# LatchDelay.net
KiCad netlist of a schematic drawn in Altium Designer
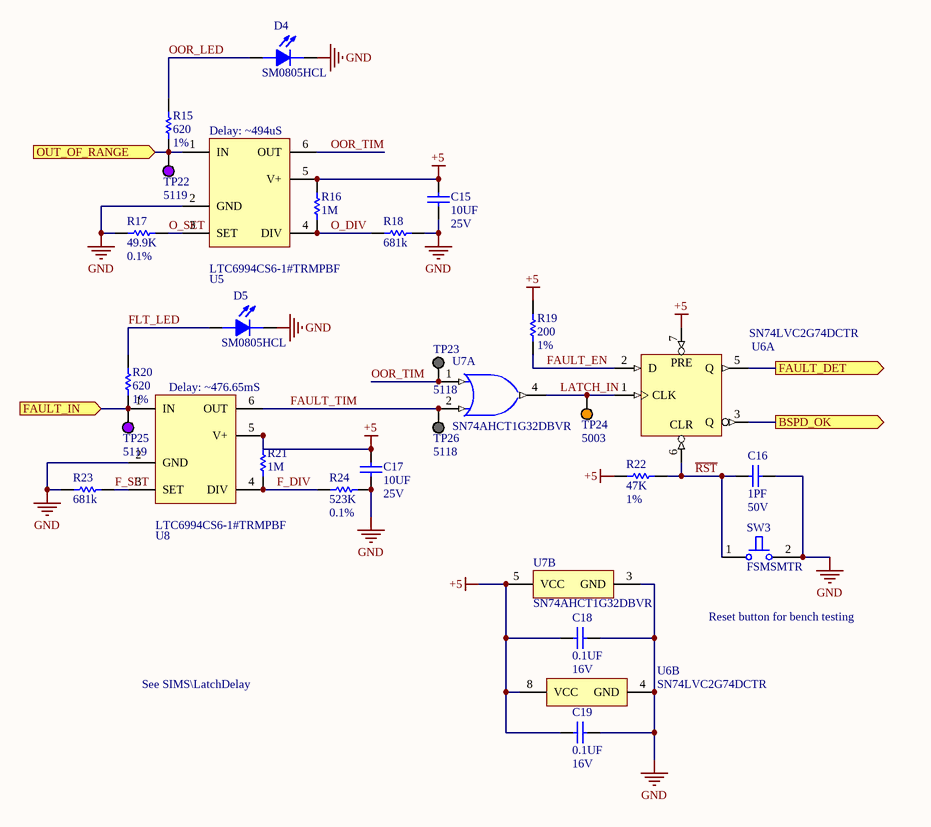
[diagram p0: LatchDelay.SchDoc]

(export (version "E")
  (design (tool "Eeschema 10.0.6"))
  (components
    (comp (ref "C15")
      (value "CAP 0603 10UF 25V 20% X5R")
      (footprint "0603_CAP")
      (description "Capacitor Surface Mount 0603 Footprint 10UF 25V 20% Tolerance Ceramic X5R")
      (fields
        (field (name "VAL") "10UF")
        (field (name "VOL") "25V")
        (field (name "MANUFACTURER") "Various")
        (field (name "VOLTAGE") "25V")
      )
      (libsource (lib "Passive Components") (part "cap"))
    )
    (comp (ref "C16")
      (value "CAP 0603 1PF 50V 0.05PF MLO")
      (footprint "0603_CAP")
      (description "Capacitor Surface Mount 0603 Footprint 1PF 50V 0.05PF Tolerance MLO")
      (fields
        (field (name "VAL") "1PF")
        (field (name "VOL") "50V")
        (field (name "MANUFACTURER") "Various")
        (field (name "VOLTAGE") "50V")
      )
      (libsource (lib "Passive Components") (part "cap"))
    )
    (comp (ref "C17")
      (value "CAP 0603 10UF 25V 20% X5R")
      (footprint "0603_CAP")
      (description "Capacitor Surface Mount 0603 Footprint 10UF 25V 20% Tolerance Ceramic X5R")
      (fields
        (field (name "VAL") "10UF")
        (field (name "VOL") "25V")
        (field (name "MANUFACTURER") "Various")
        (field (name "VOLTAGE") "25V")
      )
      (libsource (lib "Passive Components") (part "cap"))
    )
    (comp (ref "C18")
      (value "CAP 0603 0.1UF 16V 10% X7R")
      (footprint "0603_CAP")
      (description "Capacitor Surface Mount 0603 Footprint 0.1UF 16V 10% Tolerance Ceramic X7R")
      (fields
        (field (name "VAL") "0.1UF")
        (field (name "VOL") "16V")
        (field (name "MANUFACTURER") "Various")
        (field (name "VOLTAGE") "16V")
      )
      (libsource (lib "Passive Components") (part "cap"))
    )
    (comp (ref "C19")
      (value "CAP 0603 0.1UF 16V 10% X7R")
      (footprint "0603_CAP")
      (description "Capacitor Surface Mount 0603 Footprint 0.1UF 16V 10% Tolerance Ceramic X7R")
      (fields
        (field (name "VAL") "0.1UF")
        (field (name "VOL") "16V")
        (field (name "MANUFACTURER") "Various")
        (field (name "VOLTAGE") "16V")
      )
      (libsource (lib "Passive Components") (part "cap"))
    )
    (comp (ref "D4")
      (value "SM0805HCL")
      (footprint "LEDC2012X135N_SM0805HCL(Primary)")
      (description "Red 631nm LED Indication - Discrete 1.9V 0805 (2012 Metric)")
      (libsource (lib "bspd parts") (part "SM0805HCL"))
    )
    (comp (ref "D5")
      (value "SM0805HCL")
      (footprint "LEDC2012X135N_SM0805HCL(Primary)")
      (description "Red 631nm LED Indication - Discrete 1.9V 0805 (2012 Metric)")
      (libsource (lib "bspd parts") (part "SM0805HCL"))
    )
    (comp (ref "R15")
      (value "RES 0603 620 1%")
      (footprint "0603_RES")
      (description "Resistor Surface Mount, 620 Ohms, 0603 Footprint, 1% Tolerance 0.1W")
      (fields
        (field (name "VAL") "620")
        (field (name "TOL") "1%")
        (field (name "MANUFACTURER") "Various")
        (field (name "TOLERANCE") "1%")
      )
      (libsource (lib "Passive Components") (part "res"))
    )
    (comp (ref "R16")
      (value "1M")
      (footprint "RESC2013X60X35ML10T20")
      (fields (field (name "MANUFACTURER") "Yageo") (field (name "PART NUMBER") "RT0805BRE071ML"))
      (libsource (lib "Altium Content Vault") (part "RES"))
    )
    (comp (ref "R17")
      (value "RES 0603 49.9K 0.1%")
      (footprint "0603_RES")
      (description "Resistor Surface Mount, 49.9K Ohms, 0603 Footprint, 0.1% Tolerance 0.1W")
      (fields
        (field (name "VAL") "49.9K")
        (field (name "TOL") "0.1%")
        (field (name "MANUFACTURER") "Various")
        (field (name "TOLERANCE") "0.1%")
      )
      (libsource (lib "Passive Components") (part "res"))
    )
    (comp (ref "R18")
      (value "681k")
      (footprint "RESC2013X60X40NL20T25")
      (fields (field (name "MANUFACTURER") "Panasonic") (field (name "PART NUMBER") "ERA6AEB6813V"))
      (libsource (lib "Altium Content Vault") (part "RES"))
    )
    (comp (ref "R19")
      (value "RES 0603 200 1%")
      (footprint "0603_RES")
      (description "Resistor Surface Mount, 200 Ohms, 0603 Footprint, 1% Tolerance 0.1W")
      (fields
        (field (name "VAL") "200")
        (field (name "TOL") "1%")
        (field (name "MANUFACTURER") "Various")
        (field (name "TOLERANCE") "1%")
      )
      (libsource (lib "Passive Components") (part "res"))
    )
    (comp (ref "R20")
      (value "RES 0603 620 1%")
      (footprint "0603_RES")
      (description "Resistor Surface Mount, 620 Ohms, 0603 Footprint, 1% Tolerance 0.1W")
      (fields
        (field (name "VAL") "620")
        (field (name "TOL") "1%")
        (field (name "MANUFACTURER") "Various")
        (field (name "TOLERANCE") "1%")
      )
      (libsource (lib "Passive Components") (part "res"))
    )
    (comp (ref "R21")
      (value "1M")
      (footprint "RESC2013X60X35ML10T20")
      (fields (field (name "MANUFACTURER") "Yageo") (field (name "PART NUMBER") "RT0805BRE071ML"))
      (libsource (lib "Altium Content Vault") (part "RES"))
    )
    (comp (ref "R22")
      (value "RES 0603 47K 1%")
      (footprint "0603_RES")
      (description "Resistor Surface Mount, 47K Ohms, 0603 Footprint, 1% Tolerance 0.1W")
      (fields
        (field (name "VAL") "47K")
        (field (name "TOL") "1%")
        (field (name "MANUFACTURER") "Various")
        (field (name "TOLERANCE") "1%")
      )
      (libsource (lib "Passive Components") (part "res"))
    )
    (comp (ref "R23")
      (value "681k")
      (footprint "RESC2013X60X40NL20T25")
      (fields (field (name "MANUFACTURER") "Panasonic") (field (name "PART NUMBER") "ERA6AEB6813V"))
      (libsource (lib "Altium Content Vault") (part "RES"))
    )
    (comp (ref "R24")
      (value "RES 0805 523K 0.1%")
      (footprint "0805_RES")
      (description "Resistor Surface Mount, 523K Ohms, 0805 Footprint, 0.1% Tolerance 0.125W")
      (fields
        (field (name "VAL") "523K")
        (field (name "TOL") "0.1%")
        (field (name "MANUFACTURER") "Various")
        (field (name "TOLERANCE") "0.1%")
      )
      (libsource (lib "Passive Components") (part "res"))
    )
    (comp (ref "SW3")
      (value "FSMSMTR")
      (footprint "TECO-FSMSMTR_V")
      (description "FSMSM Push Button Switch, 50 mA, -35 to 85 degC, 2-Pin SMD, RoHS, Tape and Reel")
      (fields (field (name "MANUFACTURER") "TE Connectivity"))
      (libsource (lib "bspd parts") (part "FSMSMTR"))
    )
    (comp (ref "TP22")
      (value "5119")
      (footprint "KSTN-5119")
      (description "Test Point, Purple, 1-Pin THD, RoHS, Bulk")
      (fields (field (name "MANUFACTURER") "KeystoneElectronics"))
      (libsource (lib "bspd parts") (part "5119"))
    )
    (comp (ref "TP23")
      (value "5118")
      (footprint "KSTN-5118")
      (description "Test Point, Grey, 1-Pin THD, RoHS, Bulk")
      (fields (field (name "MANUFACTURER") "KeystoneElectronics"))
      (libsource (lib "bspd parts") (part "5118"))
    )
    (comp (ref "TP24")
      (value "5003")
      (footprint "KSTN-5003")
      (description "Test Point, Orange, 1-Pin THD, RoHS, Bulk")
      (fields (field (name "MANUFACTURER") "KeystoneElectronics"))
      (libsource (lib "bspd parts") (part "5003"))
    )
    (comp (ref "TP25")
      (value "5119")
      (footprint "KSTN-5119")
      (description "Test Point, Purple, 1-Pin THD, RoHS, Bulk")
      (fields (field (name "MANUFACTURER") "KeystoneElectronics"))
      (libsource (lib "bspd parts") (part "5119"))
    )
    (comp (ref "TP26")
      (value "5118")
      (footprint "KSTN-5118")
      (description "Test Point, Grey, 1-Pin THD, RoHS, Bulk")
      (fields (field (name "MANUFACTURER") "KeystoneElectronics"))
      (libsource (lib "bspd parts") (part "5118"))
    )
    (comp (ref "U5")
      (value "LTC6994CS6-1#TRMPBF")
      (footprint "Linear_Technologies_LTC6994CS6-1#TRMPBF_0")
      (description "IC DELAY LINE 8TAP PROG TSOT23-6")
      (fields
        (field (name "DIGIKEY PART NUMBER") "LTC6994CS6-1#TRMPBFCT-ND")
        (field (name "MANUFACTURER") "Linear Technologies")
      )
      (libsource (lib "bspd parts") (part "LTC6994CS6-1#TRMPBF"))
    )
    (comp (ref "U6")
      (value "SN74LVC2G74DCTR")
      (footprint "DCT0008A_M")
      (description "Single Positive-Edge-Triggered D-Type Flip-Flop with Clear and Preset, DCT0008A, LARGE T&R")
      (fields
        (field (name "GENERIC PART NUMBER") "SN74LVC2G74")
        (field (name "MANUFACTURER") "Texas Instruments")
      )
      (libsource (lib "Altium Content Vault") (part "TI-SN74XXX1G74_2G74-8"))
    )
    (comp (ref "U7")
      (value "SN74AHCT1G32DBVR")
      (footprint "DBV0005A_M")
      (description "Single 2-Input Positive-OR Gate, DBV0005A, LARGE T&R")
      (fields
        (field (name "GENERIC PART NUMBER") "SN74AHCT1G32")
        (field (name "MANUFACTURER") "Texas Instruments")
      )
      (libsource (lib "Altium Content Vault") (part "TI-SN74XXX1X32-5"))
    )
    (comp (ref "U8")
      (value "LTC6994CS6-1#TRMPBF")
      (footprint "Linear_Technologies_LTC6994CS6-1#TRMPBF_0")
      (description "IC DELAY LINE 8TAP PROG TSOT23-6")
      (fields
        (field (name "DIGIKEY PART NUMBER") "LTC6994CS6-1#TRMPBFCT-ND")
        (field (name "MANUFACTURER") "Linear Technologies")
      )
      (libsource (lib "bspd parts") (part "LTC6994CS6-1#TRMPBF"))
    )
  )
  (nets
    (net (code "1") (name "+5") (class "Default")
      (node (ref "C15") (pin "2") (pinfunction "2_2") (pintype "passive"))
      (node (ref "C17") (pin "2") (pinfunction "2_2") (pintype "passive"))
      (node (ref "C18") (pin "2") (pinfunction "2_2") (pintype "passive"))
      (node (ref "C19") (pin "2") (pinfunction "2_2") (pintype "passive"))
      (node (ref "R16") (pin "2") (pinfunction "2_2") (pintype "passive"))
      (node (ref "R19") (pin "2") (pinfunction "2_2") (pintype "passive"))
      (node (ref "R21") (pin "2") (pinfunction "2_2") (pintype "passive"))
      (node (ref "R22") (pin "1") (pinfunction "1_1") (pintype "passive"))
      (node (ref "U5") (pin "5") (pinfunction "V+_5") (pintype "passive"))
      (node (ref "U6") (pin "7") (pinfunction "~{PRE}_7") (pintype "input"))
      (node (ref "U6") (pin "8") (pinfunction "VCC_8") (pintype "power_in"))
      (node (ref "U7") (pin "5") (pinfunction "VCC_5") (pintype "power_in"))
      (node (ref "U8") (pin "5") (pinfunction "V+_5") (pintype "passive"))
    )
    (net (code "2") (name "/BSPD_OK") (class "Default")
      (node (ref "U6") (pin "3") (pinfunction "Q_3") (pintype "output"))
    )
    (net (code "3") (name "/FAULT_DET") (class "Default")
      (node (ref "U6") (pin "5") (pinfunction "Q_5") (pintype "output"))
    )
    (net (code "4") (name "/FAULT_EN") (class "Default")
      (node (ref "R19") (pin "1") (pinfunction "1_1") (pintype "passive"))
      (node (ref "U6") (pin "2") (pinfunction "D_2") (pintype "input"))
    )
    (net (code "5") (name "/FAULT_IN") (class "Default")
      (node (ref "R20") (pin "1") (pinfunction "1_1") (pintype "passive"))
      (node (ref "TP25") (pin "1") (pintype "passive"))
      (node (ref "U8") (pin "1") (pinfunction "IN_1") (pintype "passive"))
    )
    (net (code "6") (name "/FAULT_TIM") (class "Default")
      (node (ref "TP26") (pin "1") (pintype "passive"))
      (node (ref "U7") (pin "2") (pinfunction "B_2") (pintype "input"))
      (node (ref "U8") (pin "6") (pinfunction "OUT_6") (pintype "passive"))
    )
    (net (code "7") (name "/FLT_LED") (class "Default")
      (node (ref "D5") (pin "A") (pinfunction "A_A") (pintype "passive"))
      (node (ref "R20") (pin "2") (pinfunction "2_2") (pintype "passive"))
    )
    (net (code "8") (name "/F_DIV") (class "Default")
      (node (ref "R21") (pin "1") (pinfunction "1_1") (pintype "passive"))
      (node (ref "R24") (pin "1") (pinfunction "1_1") (pintype "passive"))
      (node (ref "U8") (pin "4") (pinfunction "DIV_4") (pintype "passive"))
    )
    (net (code "9") (name "/F_SET") (class "Default")
      (node (ref "R23") (pin "2") (pinfunction "2_2") (pintype "passive"))
      (node (ref "U8") (pin "3") (pinfunction "SET_3") (pintype "passive"))
    )
    (net (code "10") (name "/LATCH_IN") (class "Default")
      (node (ref "TP24") (pin "1") (pintype "passive"))
      (node (ref "U6") (pin "1") (pinfunction "CLK_1") (pintype "input"))
      (node (ref "U7") (pin "4") (pinfunction "Y_4") (pintype "output"))
    )
    (net (code "11") (name "/OOR_LED") (class "Default")
      (node (ref "D4") (pin "A") (pinfunction "A_A") (pintype "passive"))
      (node (ref "R15") (pin "2") (pinfunction "2_2") (pintype "passive"))
    )
    (net (code "12") (name "/OOR_TIM") (class "Default")
      (node (ref "TP23") (pin "1") (pintype "passive"))
      (node (ref "U5") (pin "6") (pinfunction "OUT_6") (pintype "passive"))
      (node (ref "U7") (pin "1") (pinfunction "A_1") (pintype "input"))
    )
    (net (code "13") (name "/OUT_OF_RANGE") (class "Default")
      (node (ref "R15") (pin "1") (pinfunction "1_1") (pintype "passive"))
      (node (ref "TP22") (pin "1") (pintype "passive"))
      (node (ref "U5") (pin "1") (pinfunction "IN_1") (pintype "passive"))
    )
    (net (code "14") (name "/O_DIV") (class "Default")
      (node (ref "R16") (pin "1") (pinfunction "1_1") (pintype "passive"))
      (node (ref "R18") (pin "1") (pinfunction "1_1") (pintype "passive"))
      (node (ref "U5") (pin "4") (pinfunction "DIV_4") (pintype "passive"))
    )
    (net (code "15") (name "/O_SET") (class "Default")
      (node (ref "R17") (pin "2") (pinfunction "2_2") (pintype "passive"))
      (node (ref "U5") (pin "3") (pinfunction "SET_3") (pintype "passive"))
    )
    (net (code "16") (name "/RST") (class "Default")
      (node (ref "C16") (pin "1") (pinfunction "1_1") (pintype "passive"))
      (node (ref "R22") (pin "2") (pinfunction "2_2") (pintype "passive"))
      (node (ref "SW3") (pin "1") (pinfunction "1_1") (pintype "passive"))
      (node (ref "U6") (pin "6") (pinfunction "~{CLR}_6") (pintype "input"))
    )
    (net (code "17") (name "GND") (class "Default")
      (node (ref "C15") (pin "1") (pinfunction "1_1") (pintype "passive"))
      (node (ref "C16") (pin "2") (pinfunction "2_2") (pintype "passive"))
      (node (ref "C17") (pin "1") (pinfunction "1_1") (pintype "passive"))
      (node (ref "C18") (pin "1") (pinfunction "1_1") (pintype "passive"))
      (node (ref "C19") (pin "1") (pinfunction "1_1") (pintype "passive"))
      (node (ref "D4") (pin "C") (pinfunction "C_C") (pintype "passive"))
      (node (ref "D5") (pin "C") (pinfunction "C_C") (pintype "passive"))
      (node (ref "R17") (pin "1") (pinfunction "1_1") (pintype "passive"))
      (node (ref "R18") (pin "2") (pinfunction "2_2") (pintype "passive"))
      (node (ref "R23") (pin "1") (pinfunction "1_1") (pintype "passive"))
      (node (ref "R24") (pin "2") (pinfunction "2_2") (pintype "passive"))
      (node (ref "SW3") (pin "2") (pinfunction "2_2") (pintype "passive"))
      (node (ref "U5") (pin "2") (pinfunction "GND_2") (pintype "passive"))
      (node (ref "U6") (pin "4") (pinfunction "GND_4") (pintype "power_in"))
      (node (ref "U7") (pin "3") (pinfunction "GND_3") (pintype "power_in"))
      (node (ref "U8") (pin "2") (pinfunction "GND_2") (pintype "passive"))
    )
  )
)
